# Underwater_vehicle-V3_0.net
KiCad netlist of a schematic drawn in Altium Designer
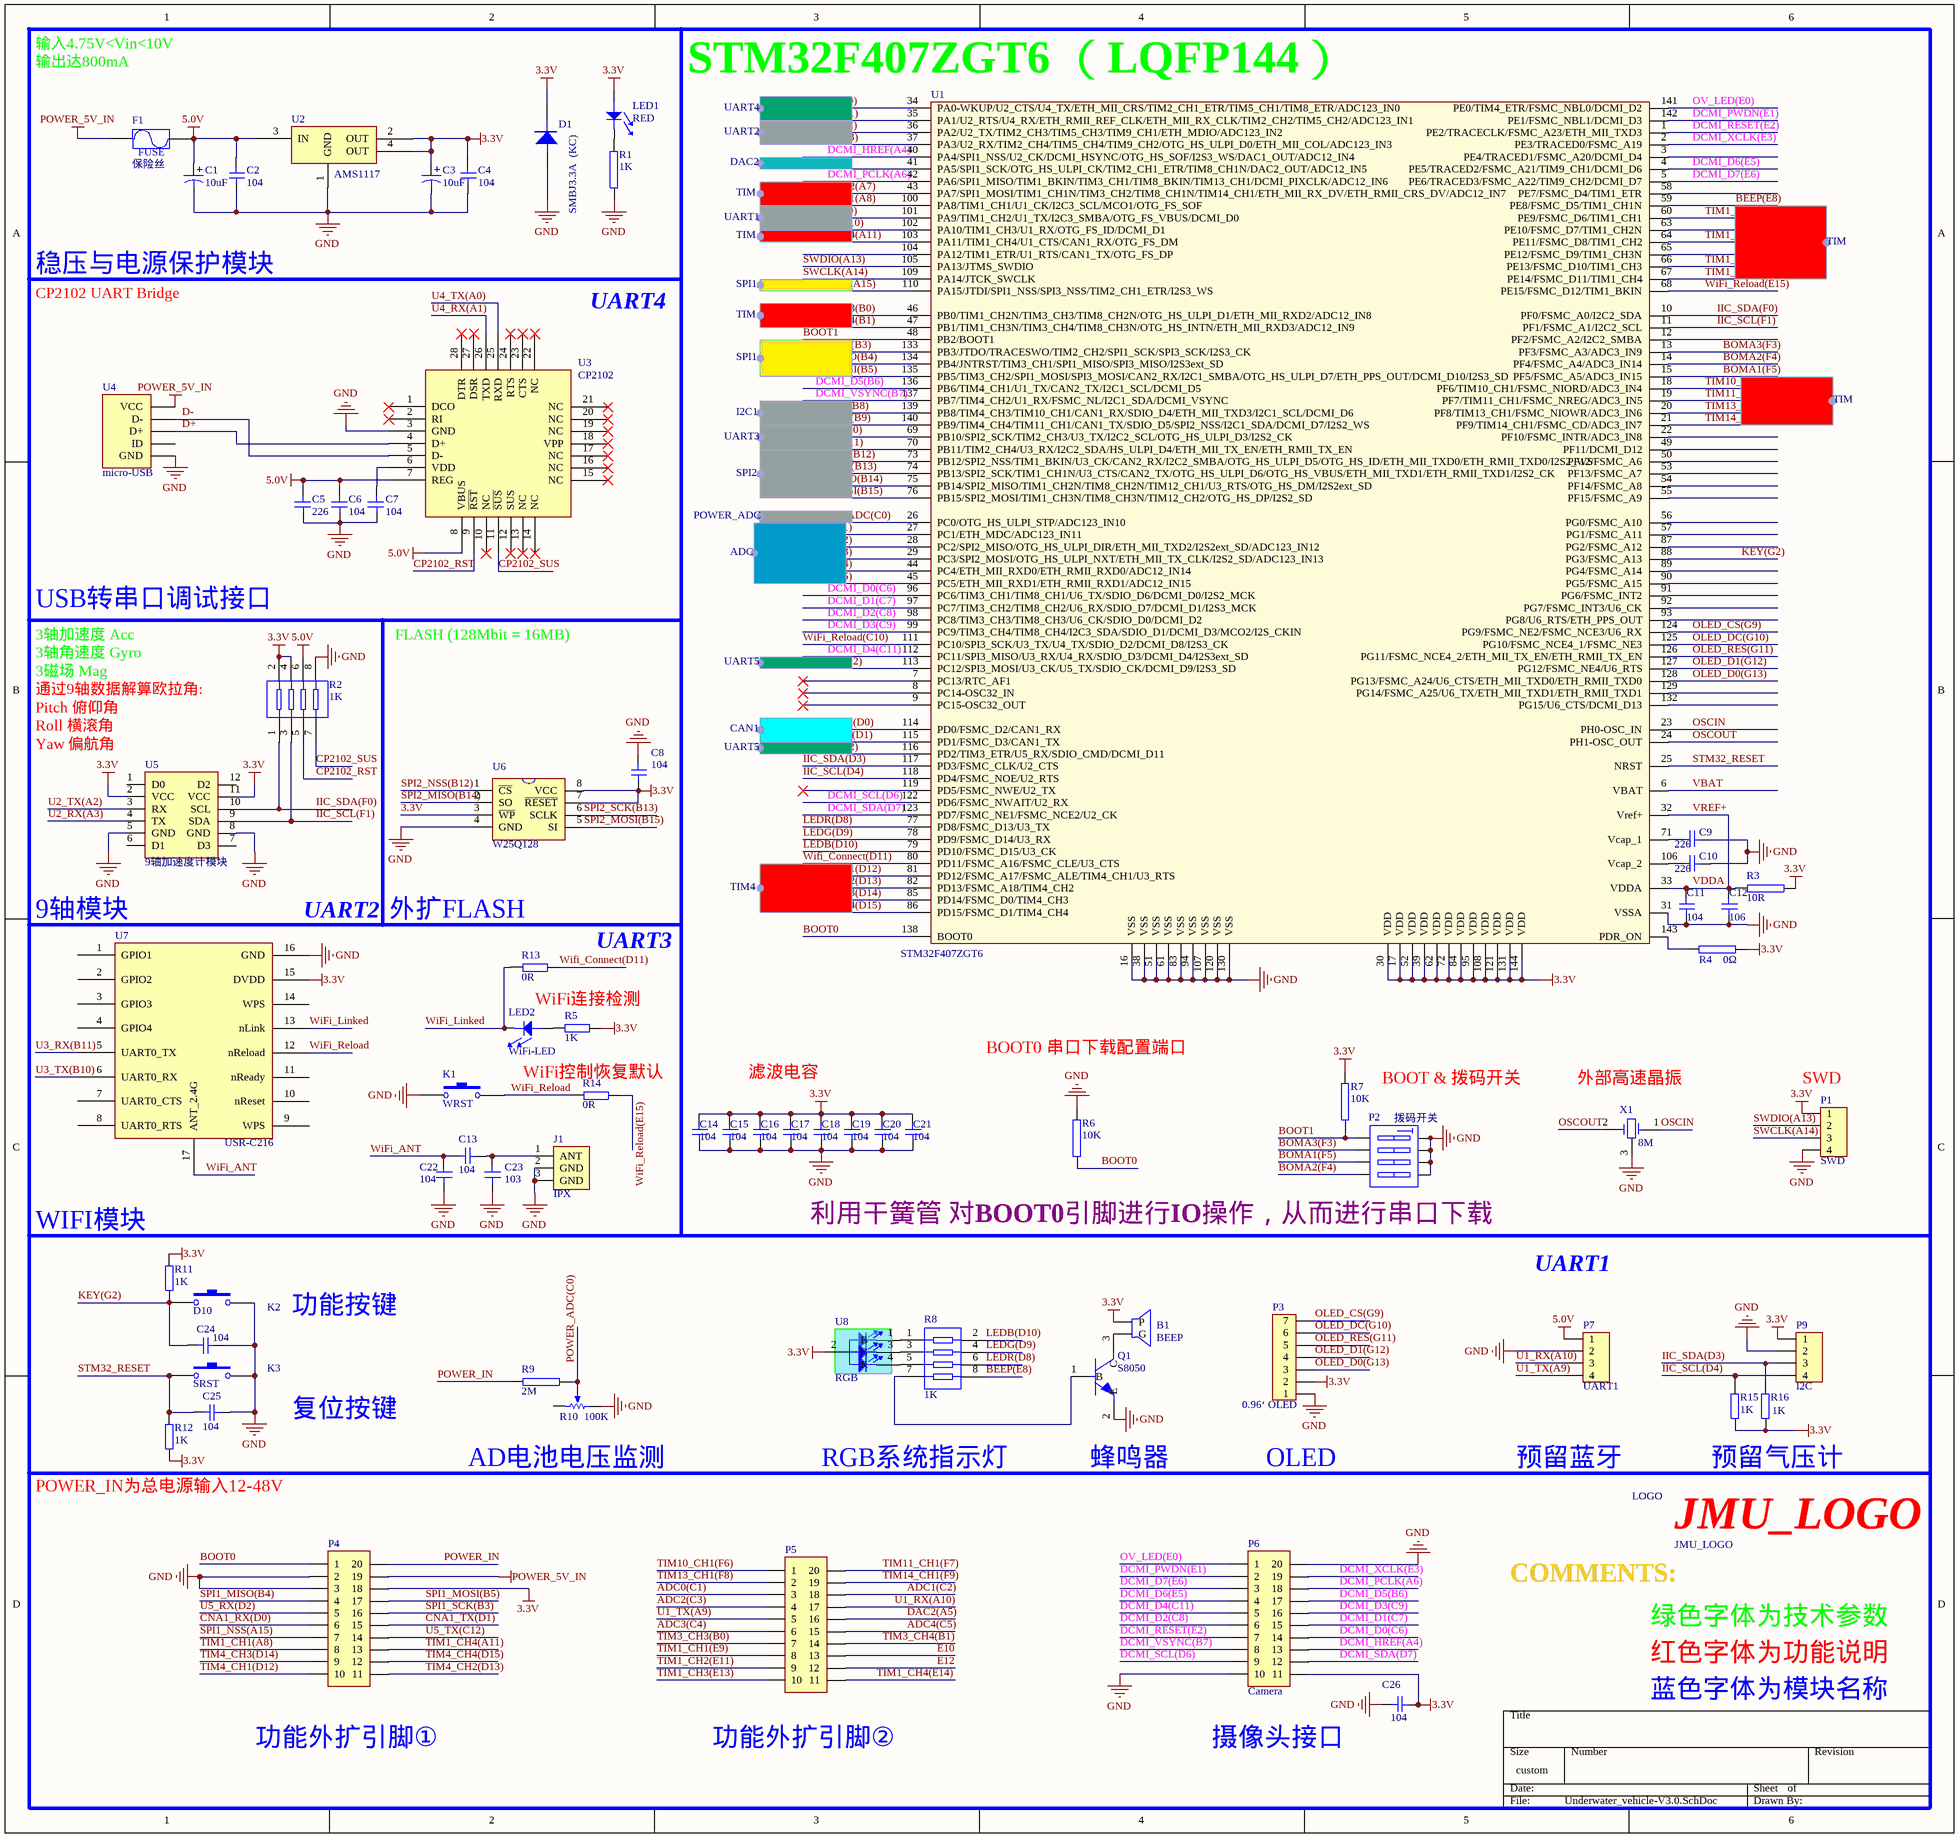
[diagram p0: Underwater_vehicle-V3.0.SchDoc]

(export (version "E")
  (design (tool "Eeschema 10.0.6"))
  (components
    (comp (ref "B1") (value "BEEP") (footprint "BUZZER") (libsource (lib "EXPLORER") (part "BEEP")))
    (comp (ref "C1")
      (value "10uF")
      (footprint "TAJ-A")
      (description "极性贴片电容")
      (libsource (lib "集大电协1.1.0") (part "Pol Cap"))
    )
    (comp (ref "C2")
      (value "104")
      (footprint "0805C")
      (description "无极贴片电容")
      (libsource (lib "集大电协1.1.0") (part "Cap1"))
    )
    (comp (ref "C3")
      (value "10uF")
      (footprint "TAJ-A")
      (description "极性贴片电容")
      (libsource (lib "集大电协1.1.0") (part "Pol Cap"))
    )
    (comp (ref "C4")
      (value "104")
      (footprint "0805C")
      (description "无极贴片电容")
      (libsource (lib "集大电协1.1.0") (part "Cap1"))
    )
    (comp (ref "C5")
      (value "226")
      (footprint "0805C")
      (description "无极贴片电容")
      (libsource (lib "集大电协1.1.0") (part "Cap1"))
    )
    (comp (ref "C6")
      (value "104")
      (footprint "0805C")
      (description "无极贴片电容")
      (libsource (lib "集大电协1.1.0") (part "Cap1"))
    )
    (comp (ref "C7")
      (value "104")
      (footprint "0805C")
      (description "无极贴片电容")
      (libsource (lib "集大电协1.1.0") (part "Cap1"))
    )
    (comp (ref "C8")
      (value "104")
      (footprint "0805C")
      (description "无极贴片电容")
      (libsource (lib "集大电协1.1.0") (part "Cap1"))
    )
    (comp (ref "C9") (value "226") (footprint "0805C") (libsource (lib "窝牛器件封装") (part "C1")))
    (comp (ref "C10") (value "226") (footprint "0805C") (libsource (lib "窝牛器件封装") (part "C1")))
    (comp (ref "C11") (value "104") (footprint "0805C") (libsource (lib "窝牛器件封装") (part "C1")))
    (comp (ref "C12") (value "106") (footprint "0805C") (libsource (lib "窝牛器件封装") (part "C1")))
    (comp (ref "C13")
      (value "104")
      (footprint "0805C")
      (description "无极贴片电容")
      (libsource (lib "集大电协1.1.2") (part "Cap1"))
    )
    (comp (ref "C14") (value "104") (footprint "0805C") (libsource (lib "窝牛器件封装") (part "C1")))
    (comp (ref "C15") (value "104") (footprint "0805C") (libsource (lib "窝牛器件封装") (part "C1")))
    (comp (ref "C16") (value "104") (footprint "0805C") (libsource (lib "窝牛器件封装") (part "C1")))
    (comp (ref "C17") (value "104") (footprint "0805C") (libsource (lib "窝牛器件封装") (part "C1")))
    (comp (ref "C18") (value "104") (footprint "0805C") (libsource (lib "窝牛器件封装") (part "C1")))
    (comp (ref "C19") (value "104") (footprint "0805C") (libsource (lib "窝牛器件封装") (part "C1")))
    (comp (ref "C20") (value "104") (footprint "0805C") (libsource (lib "窝牛器件封装") (part "C1")))
    (comp (ref "C21") (value "104") (footprint "0805C") (libsource (lib "窝牛器件封装") (part "C1")))
    (comp (ref "C22")
      (value "104")
      (footprint "0805C")
      (description "无极贴片电容")
      (libsource (lib "集大电协1.1.2") (part "Cap1"))
    )
    (comp (ref "C23")
      (value "103")
      (footprint "0805C")
      (description "无极贴片电容")
      (libsource (lib "集大电协1.1.2") (part "Cap1"))
    )
    (comp (ref "C24") (value "104") (footprint "0805C") (libsource (lib "窝牛器件封装") (part "C1")))
    (comp (ref "C25") (value "104") (footprint "0805C") (libsource (lib "窝牛器件封装") (part "C1")))
    (comp (ref "C26")
      (value "104")
      (footprint "0805C")
      (description "无极贴片电容")
      (libsource (lib "集大电协1.1.5") (part "Cap1"))
    )
    (comp (ref "D1")
      (value "SMBJ3.3A  (KC)")
      (footprint "SMBJ")
      (description "二极管")
      (libsource (lib "集大电协1.1.0") (part "Diode"))
    )
    (comp (ref "F1") (value "保险丝") (footprint "1812") (libsource (lib "集大电协1.1.2") (part "Fuse")))
    (comp (ref "J1") (value "IPX") (footprint "IPX天线底座") (libsource (lib "集大电协1.1.2") (part "IPX天线座")))
    (comp (ref "K1")
      (value "WRST")
      (footprint "贴片按键")
      (description "轻触开关")
      (libsource (lib "集大电协1.1.2") (part "轻触按键"))
    )
    (comp (ref "K2") (value "D10") (footprint "贴片按键") (libsource (lib "窝牛器件封装") (part "Key(两脚贴片)")))
    (comp (ref "K3") (value "SRST") (footprint "贴片按键") (libsource (lib "窝牛器件封装") (part "Key(两脚贴片)")))
    (comp (ref "LED1")
      (value "RED")
      (footprint "0805LED(RED)")
      (description "发光二极管")
      (libsource (lib "集大电协1.1.2") (part "LED"))
    )
    (comp (ref "LED2")
      (value "WiFi-LED")
      (footprint "0805LED(GREEN)")
      (description "发光二极管")
      (libsource (lib "集大电协1.1.2") (part "LED"))
    )
    (comp (ref "LOGO")
      (value "JMU_LOGO")
      (footprint "JMU_LOGO(1.35cm)")
      (description "LOGO")
      (libsource (lib "集大电协1.1.5") (part "JMU_LOGO"))
    )
    (comp (ref "P1")
      (value "SWD")
      (footprint "Header 4")
      (description "排针")
      (libsource (lib "集大电协1.1.0") (part "Header 4"))
    )
    (comp (ref "P2")
      (value "拨码开关")
      (footprint "拨码开关(4位贴片)")
      (description "4位拨码开关")
      (libsource (lib "集大电协1.1.2") (part "拨码开关4"))
    )
    (comp (ref "P3")
      (value "0.96‘ OLED")
      (footprint "Header 7")
      (description "排针")
      (libsource (lib "集大电协1.1.5") (part "Header 7"))
    )
    (comp (ref "P4") (value "~") (footprint "Header 10X2") (libsource (lib "集大电协1.1.2") (part "Header 10X2")))
    (comp (ref "P5") (value "~") (footprint "Header 10X2") (libsource (lib "集大电协1.1.2") (part "Header 10X2")))
    (comp (ref "P6")
      (value "Camera")
      (footprint "Header 10X2")
      (libsource (lib "集大电协1.1.2") (part "Header 10X2"))
    )
    (comp (ref "P7")
      (value "UART1")
      (footprint "Header 4(排母)")
      (description "排针")
      (libsource (lib "集大电协1.1.5") (part "Header 4"))
    )
    (comp (ref "P9")
      (value "I2C")
      (footprint "Header 4(排母)")
      (description "排针")
      (libsource (lib "集大电协1.1.5") (part "Header 4"))
    )
    (comp (ref "Q1")
      (value "S8050")
      (footprint "SOT-23")
      (description "NPN三极管")
      (libsource (lib "集大电协1.1.2") (part "NPN"))
    )
    (comp (ref "R1") (value "1K") (footprint "0805R") (libsource (lib "窝牛器件封装") (part "R1")))
    (comp (ref "R2")
      (value "1K")
      (footprint "排阻(4位贴片)")
      (description "排阻")
      (libsource (lib "集大电协1.1.2") (part "Res-4"))
    )
    (comp (ref "R3") (value "10R") (footprint "0805R") (libsource (lib "窝牛器件封装") (part "R1")))
    (comp (ref "R4") (value "0Ω") (footprint "0805R") (libsource (lib "窝牛器件封装") (part "R1")))
    (comp (ref "R5")
      (value "1K")
      (footprint "0805R")
      (description "电阻")
      (libsource (lib "集大电协1.1.2") (part "Res"))
    )
    (comp (ref "R6") (value "10K") (footprint "0805R") (libsource (lib "窝牛器件封装") (part "R1")))
    (comp (ref "R7") (value "10K") (footprint "0805R") (libsource (lib "窝牛器件封装") (part "R1")))
    (comp (ref "R8")
      (value "1K")
      (footprint "排阻(4位贴片)")
      (description "排阻")
      (libsource (lib "集大电协1.1.2") (part "Res-4"))
    )
    (comp (ref "R9") (value "2M") (footprint "0805R") (libsource (lib "窝牛器件封装") (part "R1")))
    (comp (ref "R10")
      (value "100K")
      (footprint "3296w")
      (description "电位器")
      (libsource (lib "集大电协1.1.2") (part "RPot"))
    )
    (comp (ref "R11")
      (value "1K")
      (footprint "0805R")
      (description "电阻")
      (libsource (lib "集大电协1.1.5") (part "Res"))
    )
    (comp (ref "R12")
      (value "1K")
      (footprint "0805R")
      (description "电阻")
      (libsource (lib "集大电协1.1.5") (part "Res"))
    )
    (comp (ref "R13")
      (value "0R")
      (footprint "0805R")
      (description "电阻")
      (libsource (lib "集大电协1.1.5") (part "Res"))
    )
    (comp (ref "R14")
      (value "0R")
      (footprint "0805R")
      (description "电阻")
      (libsource (lib "集大电协1.1.5") (part "Res"))
    )
    (comp (ref "R15")
      (value "1K")
      (footprint "0805R")
      (description "电阻")
      (libsource (lib "集大电协1.2") (part "Res"))
    )
    (comp (ref "R16")
      (value "1K")
      (footprint "0805R")
      (description "电阻")
      (libsource (lib "集大电协1.2") (part "Res"))
    )
    (comp (ref "U1")
      (value "STM32F407ZGT6")
      (footprint "LQFP-144")
      (libsource (lib "窝牛器件封装") (part "STM32F407ZET6"))
    )
    (comp (ref "U2")
      (value "AMS1117")
      (footprint "SOT-223")
      (description "电源芯片")
      (libsource (lib "集大电协1.1.0") (part "AMS1117-3.3V/5.0V"))
    )
    (comp (ref "U3")
      (value "CP2102")
      (footprint "QFN-28")
      (description "USB转串口芯片")
      (libsource (lib "集大电协1.1.0") (part "CP2102"))
    )
    (comp (ref "U4")
      (value "micro-USB")
      (footprint "Micro-USB (兼容牛角)")
      (description "USB接口")
      (libsource (lib "集大电协1.1.2") (part "micro-USB"))
    )
    (comp (ref "U5") (value "9轴加速度计模块") (footprint "9轴加速度计") (libsource (lib "窝牛器件封装") (part "9轴加速度计")))
    (comp (ref "U6")
      (value "W25Q128")
      (footprint "SOW-8")
      (description "FLASH芯片")
      (libsource (lib "集大电协1.1.0") (part "W25Q128"))
    )
    (comp (ref "U7")
      (value "USR-C216")
      (footprint "USR-C216")
      (libsource (lib "集大电协1.1.2") (part "USR-C216"))
    )
    (comp (ref "U8") (value "RGB") (footprint "RGB-3528") (libsource (lib "集大电协1.1.2") (part "RGB")))
    (comp (ref "X1") (value "8M") (footprint "三脚贴片8M晶振") (libsource (lib "集大电协1.1.2") (part "XTAL三脚贴片晶振")))
  )
  (nets
    (net (code "1") (name "/ADC0(C1)") (class "Default")
      (node (ref "P5") (pin "3") (pinfunction "3_3") (pintype "passive"))
      (node (ref "U1") (pin "27") (pinfunction "PC1/ETH_MDC/ADC123_IN11_27") (pintype "passive"))
    )
    (net (code "2") (name "/ADC1(C2)") (class "Default")
      (node (ref "P5") (pin "18") (pinfunction "18_18") (pintype "passive"))
      (node (ref "U1") (pin "28") (pinfunction "PC2/SPI2_MISO/OTG_HS_ULPI_DIR/ETH_MII_TXD2/I2S2ext_SD/ADC123_IN12_28") (pintype "passive"))
    )
    (net (code "3") (name "/ADC2(C3)") (class "Default")
      (node (ref "P5") (pin "4") (pinfunction "4_4") (pintype "passive"))
      (node (ref "U1") (pin "29") (pinfunction "PC3/SPI2_MOSI/OTG_HS_ULPI_NXT/ETH_MII_TX_CLK/I2S2_SD/ADC123_IN13_29") (pintype "passive"))
    )
    (net (code "4") (name "/ADC3(C4)") (class "Default")
      (node (ref "P5") (pin "6") (pinfunction "6_6") (pintype "passive"))
      (node (ref "U1") (pin "44") (pinfunction "PC4/ETH_MII_RXD0/ETH_RMII_RXD0/ADC12_IN14_44") (pintype "passive"))
    )
    (net (code "5") (name "/ADC4(C5)") (class "Default")
      (node (ref "P5") (pin "15") (pinfunction "15_15") (pintype "passive"))
      (node (ref "U1") (pin "45") (pinfunction "PC5/ETH_MII_RXD1/ETH_RMII_RXD1/ADC12_IN15_45") (pintype "passive"))
    )
    (net (code "6") (name "/BEEP(E8)") (class "Default")
      (node (ref "R8") (pin "8") (pinfunction "8_8") (pintype "passive"))
      (node (ref "U1") (pin "59") (pinfunction "PE8/FSMC_D5/TIM1_CH1N_59") (pintype "passive"))
    )
    (net (code "7") (name "/BOMA1(F5)") (class "Default")
      (node (ref "P2") (pin "3") (pinfunction "A3_3") (pintype "passive"))
      (node (ref "U1") (pin "15") (pinfunction "PF5/FSMC_A5/ADC3_IN15_15") (pintype "passive"))
    )
    (net (code "8") (name "/BOMA2(F4)") (class "Default")
      (node (ref "P2") (pin "4") (pinfunction "A4_4") (pintype "passive"))
      (node (ref "U1") (pin "14") (pinfunction "PF4/FSMC_A4/ADC3_IN14_14") (pintype "passive"))
    )
    (net (code "9") (name "/BOMA3(F3)") (class "Default")
      (node (ref "P2") (pin "2") (pinfunction "A2_2") (pintype "passive"))
      (node (ref "U1") (pin "13") (pinfunction "PF3/FSMC_A3/ADC3_IN9_13") (pintype "passive"))
    )
    (net (code "10") (name "/BOOT0") (class "Default")
      (node (ref "P4") (pin "1") (pinfunction "1_1") (pintype "passive"))
      (node (ref "R6") (pin "1") (pinfunction "1_1") (pintype "passive"))
      (node (ref "U1") (pin "138") (pinfunction "BOOT0_138") (pintype "passive"))
    )
    (net (code "11") (name "/BOOT1") (class "Default")
      (node (ref "P2") (pin "1") (pinfunction "A1_1") (pintype "passive"))
      (node (ref "R7") (pin "1") (pinfunction "1_1") (pintype "passive"))
      (node (ref "U1") (pin "48") (pinfunction "PB2/BOOT1_48") (pintype "passive"))
    )
    (net (code "12") (name "/CNA1_RX(D0)") (class "Default")
      (node (ref "P4") (pin "6") (pinfunction "6_6") (pintype "passive"))
      (node (ref "U1") (pin "114") (pinfunction "PD0/FSMC_D2/CAN1_RX_114") (pintype "passive"))
    )
    (net (code "13") (name "/CNA1_TX(D1)") (class "Default")
      (node (ref "P4") (pin "15") (pinfunction "15_15") (pintype "passive"))
      (node (ref "U1") (pin "115") (pinfunction "PD1/FSMC_D3/CAN1_TX_115") (pintype "passive"))
    )
    (net (code "14") (name "/CP2102_RST") (class "Default")
      (node (ref "R2") (pin "5") (pinfunction "5_5") (pintype "passive"))
      (node (ref "U3") (pin "9") (pinfunction "~{RST}_9") (pintype "passive"))
    )
    (net (code "15") (name "/CP2102_SUS") (class "Default")
      (node (ref "R2") (pin "7") (pinfunction "7_7") (pintype "passive"))
      (node (ref "U3") (pin "11") (pinfunction "~{SUS}_11") (pintype "passive"))
    )
    (net (code "16") (name "/D+") (class "Default")
      (node (ref "U3") (pin "4") (pinfunction "D+_4") (pintype "passive"))
      (node (ref "U4") (pin "3") (pinfunction "D+_3") (pintype "power_in"))
    )
    (net (code "17") (name "/D-") (class "Default")
      (node (ref "U3") (pin "5") (pinfunction "D-_5") (pintype "passive"))
      (node (ref "U4") (pin "2") (pinfunction "D-_2") (pintype "power_in"))
    )
    (net (code "18") (name "/DAC2(A5)") (class "Default")
      (node (ref "P5") (pin "16") (pinfunction "16_16") (pintype "passive"))
      (node (ref "U1") (pin "41") (pinfunction "PA5/SPI1_SCK/OTG_HS_ULPI_CK/TIM2_CH1_ETR/TIM8_CH1N/DAC2_OUT/ADC12_IN5_41") (pintype "passive"))
    )
    (net (code "19") (name "/DCMI_D0(C6)") (class "Default")
      (node (ref "P6") (pin "14") (pinfunction "14_14") (pintype "passive"))
      (node (ref "U1") (pin "96") (pinfunction "PC6/TIM3_CH1/TIM8_CH1/U6_TX/SDIO_D6/DCMI_D0/I2S2_MCK_96") (pintype "passive"))
    )
    (net (code "20") (name "/DCMI_D1(C7)") (class "Default")
      (node (ref "P6") (pin "15") (pinfunction "15_15") (pintype "passive"))
      (node (ref "U1") (pin "97") (pinfunction "PC7/TIM3_CH2/TIM8_CH2/U6_RX/SDIO_D7/DCMI_D1/I2S3_MCK_97") (pintype "passive"))
    )
    (net (code "21") (name "/DCMI_D2(C8)") (class "Default")
      (node (ref "P6") (pin "6") (pinfunction "6_6") (pintype "passive"))
      (node (ref "U1") (pin "98") (pinfunction "PC8/TIM3_CH3/TIM8_CH3/U6_CK/SDIO_D0/DCMI_D2_98") (pintype "passive"))
    )
    (net (code "22") (name "/DCMI_D3(C9)") (class "Default")
      (node (ref "P6") (pin "16") (pinfunction "16_16") (pintype "passive"))
      (node (ref "U1") (pin "99") (pinfunction "PC9/TIM3_CH4/TIM8_CH4/I2C3_SDA/SDIO_D1/DCMI_D3/MCO2/I2S_CKIN_99") (pintype "passive"))
    )
    (net (code "23") (name "/DCMI_D4(C11)") (class "Default")
      (node (ref "P6") (pin "5") (pinfunction "5_5") (pintype "passive"))
      (node (ref "U1") (pin "112") (pinfunction "PC11/SPI3_MISO/U3_RX/U4_RX/SDIO_D3/DCMI_D4/I2S3ext_SD_112") (pintype "passive"))
    )
    (net (code "24") (name "/DCMI_D5(B6)") (class "Default")
      (node (ref "P6") (pin "17") (pinfunction "17_17") (pintype "passive"))
      (node (ref "U1") (pin "136") (pinfunction "PB6/TIM4_CH1/U1_TX/CAN2_TX/I2C1_SCL/DCMI_D5_136") (pintype "passive"))
    )
    (net (code "25") (name "/DCMI_D6(E5)") (class "Default")
      (node (ref "P6") (pin "4") (pinfunction "4_4") (pintype "passive"))
      (node (ref "U1") (pin "4") (pinfunction "PE5/TRACED2/FSMC_A21/TIM9_CH1/DCMI_D6_4") (pintype "passive"))
    )
    (net (code "26") (name "/DCMI_D7(E6)") (class "Default")
      (node (ref "P6") (pin "3") (pinfunction "3_3") (pintype "passive"))
      (node (ref "U1") (pin "5") (pinfunction "PE6/TRACED3/FSMC_A22/TIM9_CH2/DCMI_D7_5") (pintype "passive"))
    )
    (net (code "27") (name "/DCMI_HREF(A4)") (class "Default")
      (node (ref "P6") (pin "13") (pinfunction "13_13") (pintype "passive"))
      (node (ref "U1") (pin "40") (pinfunction "PA4/SPI1_NSS/U2_CK/DCMI_HSYNC/OTG_HS_SOF/I2S3_WS/DAC1_OUT/ADC12_IN4_40") (pintype "passive"))
    )
    (net (code "28") (name "/DCMI_PCLK(A6)") (class "Default")
      (node (ref "P6") (pin "18") (pinfunction "18_18") (pintype "passive"))
      (node (ref "U1") (pin "42") (pinfunction "PA6/SPI1_MISO/TIM1_BKIN/TIM3_CH1/TIM8_BKIN/TIM13_CH1/DCMI_PIXCLK/ADC12_IN6_42") (pintype "passive"))
    )
    (net (code "29") (name "/DCMI_PWDN(E1)") (class "Default")
      (node (ref "P6") (pin "2") (pinfunction "2_2") (pintype "passive"))
      (node (ref "U1") (pin "142") (pinfunction "PE1/FSMC_NBL1/DCMI_D3_142") (pintype "passive"))
    )
    (net (code "30") (name "/DCMI_RESET(E2)") (class "Default")
      (node (ref "P6") (pin "7") (pinfunction "7_7") (pintype "passive"))
      (node (ref "U1") (pin "1") (pinfunction "PE2/TRACECLK/FSMC_A23/ETH_MII_TXD3_1") (pintype "passive"))
    )
    (net (code "31") (name "/DCMI_SCL(D6)") (class "Default")
      (node (ref "P6") (pin "9") (pinfunction "9_9") (pintype "passive"))
      (node (ref "U1") (pin "122") (pinfunction "PD6/FSMC_NWAIT/U2_RX_122") (pintype "passive"))
    )
    (net (code "32") (name "/DCMI_SDA(D7)") (class "Default")
      (node (ref "P6") (pin "12") (pinfunction "12_12") (pintype "passive"))
      (node (ref "U1") (pin "123") (pinfunction "PD7/FSMC_NE1/FSMC_NCE2/U2_CK_123") (pintype "passive"))
    )
    (net (code "33") (name "/DCMI_VSYNC(B7)") (class "Default")
      (node (ref "P6") (pin "8") (pinfunction "8_8") (pintype "passive"))
      (node (ref "U1") (pin "137") (pinfunction "PB7/TIM4_CH2/U1_RX/FSMC_NL/I2C1_SDA/DCMI_VSYNC_137") (pintype "passive"))
    )
    (net (code "34") (name "/DCMI_XCLK(E3)") (class "Default")
      (node (ref "P6") (pin "19") (pinfunction "19_19") (pintype "passive"))
      (node (ref "U1") (pin "2") (pinfunction "PE3/TRACED0/FSMC_A19_2") (pintype "passive"))
    )
    (net (code "35") (name "/E10") (class "Default")
      (node (ref "P5") (pin "13") (pinfunction "13_13") (pintype "passive"))
      (node (ref "U1") (pin "63") (pinfunction "PE10/FSMC_D7/TIM1_CH2N_63") (pintype "passive"))
    )
    (net (code "36") (name "/E12") (class "Default")
      (node (ref "P5") (pin "12") (pinfunction "12_12") (pintype "passive"))
      (node (ref "U1") (pin "65") (pinfunction "PE12/FSMC_D9/TIM1_CH3N_65") (pintype "passive"))
    )
    (net (code "37") (name "/IIC1_SCL(B8)") (class "Default")
      (node (ref "U1") (pin "139") (pinfunction "PB8/TIM4_CH3/TIM10_CH1/CAN1_RX/SDIO_D4/ETH_MII_TXD3/I2C1_SCL/DCMI_D6_139") (pintype "passive"))
    )
    (net (code "38") (name "/IIC1_SDA(B9)") (class "Default")
      (node (ref "U1") (pin "140") (pinfunction "PB9/TIM4_CH4/TIM11_CH1/CAN1_TX/SDIO_D5/SPI2_NSS/I2C1_SDA/DCMI_D7/I2S2_WS_140") (pintype "passive"))
    )
    (net (code "39") (name "/IIC_SCL(D4)") (class "Default")
      (node (ref "P9") (pin "4") (pinfunction "4_4") (pintype "passive"))
      (node (ref "R15") (pin "2") (pinfunction "2_2") (pintype "passive"))
      (node (ref "U1") (pin "118") (pinfunction "PD4/FSMC_NOE/U2_RTS_118") (pintype "passive"))
    )
    (net (code "40") (name "/IIC_SCL(F1)") (class "Default")
      (node (ref "R2") (pin "3") (pinfunction "3_3") (pintype "passive"))
      (node (ref "U1") (pin "11") (pinfunction "PF1/FSMC_A1/I2C2_SCL_11") (pintype "passive"))
      (node (ref "U5") (pin "9") (pinfunction "SDA_9") (pintype "passive"))
    )
    (net (code "41") (name "/IIC_SDA(D3)") (class "Default")
      (node (ref "P9") (pin "3") (pinfunction "3_3") (pintype "passive"))
      (node (ref "R16") (pin "2") (pinfunction "2_2") (pintype "passive"))
      (node (ref "U1") (pin "117") (pinfunction "PD3/FSMC_CLK/U2_CTS_117") (pintype "passive"))
    )
    (net (code "42") (name "/IIC_SDA(F0)") (class "Default")
      (node (ref "R2") (pin "1") (pinfunction "1_1") (pintype "passive"))
      (node (ref "U1") (pin "10") (pinfunction "PF0/FSMC_A0/I2C2_SDA_10") (pintype "passive"))
      (node (ref "U5") (pin "10") (pinfunction "SCL_10") (pintype "passive"))
    )
    (net (code "43") (name "/KEY(G2)") (class "Default")
      (node (ref "C24") (pin "1") (pinfunction "1_1") (pintype "passive"))
      (node (ref "K2") (pin "1") (pinfunction "1_1") (pintype "passive"))
      (node (ref "R11") (pin "1") (pinfunction "1_1") (pintype "passive"))
      (node (ref "U1") (pin "88") (pinfunction "PG3/FSMC_A13_88") (pintype "passive"))
    )
    (net (code "44") (name "/LEDB(D10)") (class "Default")
      (node (ref "R8") (pin "2") (pinfunction "2_2") (pintype "passive"))
      (node (ref "U1") (pin "79") (pinfunction "PD10/FSMC_D15/U3_CK_79") (pintype "passive"))
    )
    (net (code "45") (name "/LEDG(D9)") (class "Default")
      (node (ref "R8") (pin "4") (pinfunction "4_4") (pintype "passive"))
      (node (ref "U1") (pin "78") (pinfunction "PD9/FSMC_D14/U3_RX_78") (pintype "passive"))
    )
    (net (code "46") (name "/LEDR(D8)") (class "Default")
      (node (ref "R8") (pin "6") (pinfunction "6_6") (pintype "passive"))
      (node (ref "U1") (pin "77") (pinfunction "PD8/FSMC_D13/U3_TX_77") (pintype "passive"))
    )
    (net (code "47") (name "/OLED_CS(G9)") (class "Default")
      (node (ref "P3") (pin "7") (pinfunction "7_7") (pintype "passive"))
      (node (ref "U1") (pin "124") (pinfunction "PG9/FSMC_NE2/FSMC_NCE3/U6_RX_124") (pintype "passive"))
    )
    (net (code "48") (name "/OLED_D0(G13)") (class "Default")
      (node (ref "P3") (pin "3") (pinfunction "3_3") (pintype "passive"))
      (node (ref "U1") (pin "128") (pinfunction "PG13/FSMC_A24/U6_CTS/ETH_MII_TXD0/ETH_RMII_TXD0_128") (pintype "passive"))
    )
    (net (code "49") (name "/OLED_D1(G12)") (class "Default")
      (node (ref "P3") (pin "4") (pinfunction "4_4") (pintype "passive"))
      (node (ref "U1") (pin "127") (pinfunction "PG12/FSMC_NE4/U6_RTS_127") (pintype "passive"))
    )
    (net (code "50") (name "/OLED_DC(G10)") (class "Default")
      (node (ref "P3") (pin "6") (pinfunction "6_6") (pintype "passive"))
      (node (ref "U1") (pin "125") (pinfunction "PG10/FSMC_NCE4_1/FSMC_NE3_125") (pintype "passive"))
    )
    (net (code "51") (name "/OLED_RES(G11)") (class "Default")
      (node (ref "P3") (pin "5") (pinfunction "5_5") (pintype "passive"))
      (node (ref "U1") (pin "126") (pinfunction "PG11/FSMC_NCE4_2/ETH_MII_TX_EN/ETH_RMII_TX_EN_126") (pintype "passive"))
    )
    (net (code "52") (name "/OSCIN") (class "Default")
      (node (ref "U1") (pin "23") (pinfunction "PH0-OSC_IN_23") (pintype "passive"))
      (node (ref "X1") (pin "1") (pinfunction "1_1") (pintype "passive"))
    )
    (net (code "53") (name "/OSCOUT") (class "Default")
      (node (ref "U1") (pin "24") (pinfunction "PH1-OSC_OUT_24") (pintype "passive"))
      (node (ref "X1") (pin "2") (pinfunction "2_2") (pintype "passive"))
    )
    (net (code "54") (name "/OV_LED(E0)") (class "Default")
      (node (ref "P6") (pin "1") (pinfunction "1_1") (pintype "passive"))
      (node (ref "U1") (pin "141") (pinfunction "PE0/TIM4_ETR/FSMC_NBL0/DCMI_D2_141") (pintype "passive"))
    )
    (net (code "55") (name "/POWER_ADC(C0)") (class "Default")
      (node (ref "R10") (pin "2") (pinfunction "TAP_2") (pintype "passive"))
      (node (ref "R9") (pin "2") (pinfunction "2_2") (pintype "passive"))
      (node (ref "U1") (pin "26") (pinfunction "PC0/OTG_HS_ULPI_STP/ADC123_IN10_26") (pintype "passive"))
    )
    (net (code "56") (name "/POWER_IN") (class "Default")
      (node (ref "P4") (pin "20") (pinfunction "20_20") (pintype "passive"))
      (node (ref "R9") (pin "1") (pinfunction "1_1") (pintype "passive"))
    )
    (net (code "57") (name "/SPI1_MISO(B4)") (class "Default")
      (node (ref "P4") (pin "4") (pinfunction "4_4") (pintype "passive"))
      (node (ref "U1") (pin "134") (pinfunction "PB4/JNTRST/TIM3_CH1/SPI1_MISO/SPI3_MISO/I2S3ext_SD_134") (pintype "passive"))
    )
    (net (code "58") (name "/SPI1_MOSI(B5)") (class "Default")
      (node (ref "P4") (pin "17") (pinfunction "17_17") (pintype "passive"))
      (node (ref "U1") (pin "135") (pinfunction "PB5/TIM3_CH2/SPI1_MOSI/SPI3_MOSI/CAN2_RX/I2C1_SMBA/OTG_HS_ULPI_D7/ETH_PPS_OUT/DCMI_D10/I2S3_SD_135") (pintype "passive"))
    )
    (net (code "59") (name "/SPI1_NSS(A15)") (class "Default")
      (node (ref "P4") (pin "7") (pinfunction "7_7") (pintype "passive"))
      (node (ref "U1") (pin "110") (pinfunction "PA15/JTDI/SPI1_NSS/SPI3_NSS/TIM2_CH1_ETR/I2S3_WS_110") (pintype "passive"))
    )
    (net (code "60") (name "/SPI1_SCK(B3)") (class "Default")
      (node (ref "P4") (pin "16") (pinfunction "16_16") (pintype "passive"))
      (node (ref "U1") (pin "133") (pinfunction "PB3/JTDO/TRACESWO/TIM2_CH2/SPI1_SCK/SPI3_SCK/I2S3_CK_133") (pintype "passive"))
    )
    (net (code "61") (name "/SPI2_MISO(B14)") (class "Default")
      (node (ref "U1") (pin "75") (pinfunction "PB14/SPI2_MISO/TIM1_CH2N/TIM8_CH2N/TIM12_CH1/U3_RTS/OTG_HS_DM/I2S2ext_SD_75") (pintype "passive"))
      (node (ref "U6") (pin "2") (pinfunction "SO_2") (pintype "passive"))
    )
    (net (code "62") (name "/SPI2_MOSI(B15)") (class "Default")
      (node (ref "U1") (pin "76") (pinfunction "PB15/SPI2_MOSI/TIM1_CH3N/TIM8_CH3N/TIM12_CH2/OTG_HS_DP/I2S2_SD_76") (pintype "passive"))
      (node (ref "U6") (pin "5") (pinfunction "SI_5") (pintype "passive"))
    )
    (net (code "63") (name "/SPI2_NSS(B12)") (class "Default")
      (node (ref "U1") (pin "73") (pinfunction "PB12/SPI2_NSS/TIM1_BKIN/U3_CK/CAN2_RX/I2C2_SMBA/OTG_HS_ULPI_D5/OTG_HS_ID/ETH_MII_TXD0/ETH_RMII_TXD0/I2S2_WS_73") (pintype "passive"))
      (node (ref "U6") (pin "1") (pinfunction "~{CS}_1") (pintype "passive"))
    )
    (net (code "64") (name "/SPI2_SCK(B13)") (class "Default")
      (node (ref "U1") (pin "74") (pinfunction "PB13/SPI2_SCK/TIM1_CH1N/U3_CTS/CAN2_TX/OTG_HS_ULPI_D6/OTG_HS_VBUS/ETH_MII_TXD1/ETH_RMII_TXD1/I2S2_CK_74") (pintype "passive"))
      (node (ref "U6") (pin "6") (pinfunction "SCLK_6") (pintype "passive"))
    )
    (net (code "65") (name "/STM32_RESET") (class "Default")
      (node (ref "C25") (pin "1") (pinfunction "1_1") (pintype "passive"))
      (node (ref "K3") (pin "1") (pinfunction "1_1") (pintype "passive"))
      (node (ref "R12") (pin "2") (pinfunction "2_2") (pintype "passive"))
      (node (ref "U1") (pin "25") (pinfunction "NRST_25") (pintype "passive"))
    )
    (net (code "66") (name "/SWCLK(A14)") (class "Default")
      (node (ref "P1") (pin "3") (pinfunction "3_3") (pintype "passive"))
      (node (ref "U1") (pin "109") (pinfunction "PA14/JTCK_SWCLK_109") (pintype "passive"))
    )
    (net (code "67") (name "/SWDIO(A13)") (class "Default")
      (node (ref "P1") (pin "2") (pinfunction "2_2") (pintype "passive"))
      (node (ref "U1") (pin "105") (pinfunction "PA13/JTMS_SWDIO_105") (pintype "passive"))
    )
    (net (code "68") (name "/TIM1_CH1(A8)") (class "Default")
      (node (ref "P4") (pin "8") (pinfunction "8_8") (pintype "passive"))
      (node (ref "U1") (pin "100") (pinfunction "PA8/TIM1_CH1/U1_CK/I2C3_SCL/MCO1/OTG_FS_SOF_100") (pintype "passive"))
    )
    (net (code "69") (name "/TIM1_CH1(E9)") (class "Default")
      (node (ref "P5") (pin "8") (pinfunction "8_8") (pintype "passive"))
      (node (ref "U1") (pin "60") (pinfunction "PE9/FSMC_D6/TIM1_CH1_60") (pintype "passive"))
    )
    (net (code "70") (name "/TIM1_CH2(E11)") (class "Default")
      (node (ref "P5") (pin "9") (pinfunction "9_9") (pintype "passive"))
      (node (ref "U1") (pin "64") (pinfunction "PE11/FSMC_D8/TIM1_CH2_64") (pintype "passive"))
    )
    (net (code "71") (name "/TIM1_CH3(E13)") (class "Default")
      (node (ref "P5") (pin "10") (pinfunction "10_10") (pintype "passive"))
      (node (ref "U1") (pin "66") (pinfunction "PE13/FSMC_D10/TIM1_CH3_66") (pintype "passive"))
    )
    (net (code "72") (name "/TIM1_CH4(A11)") (class "Default")
      (node (ref "P4") (pin "13") (pinfunction "13_13") (pintype "passive"))
      (node (ref "U1") (pin "103") (pinfunction "PA11/TIM1_CH4/U1_CTS/CAN1_RX/OTG_FS_DM_103") (pintype "passive"))
    )
    (net (code "73") (name "/TIM1_CH4(E14)") (class "Default")
      (node (ref "P5") (pin "11") (pinfunction "11_11") (pintype "passive"))
      (node (ref "U1") (pin "67") (pinfunction "PE14/FSMC_D11/TIM1_CH4_67") (pintype "passive"))
    )
    (net (code "74") (name "/TIM3_CH2(A7)") (class "Default")
      (node (ref "U1") (pin "43") (pinfunction "PA7/SPI1_MOSI/TIM1_CH1N/TIM3_CH2/TIM8_CH1N/TIM14_CH1/ETH_MII_RX_DV/ETH_RMII_CRS_DV/ADC12_IN7_43") (pintype "passive"))
    )
    (net (code "75") (name "/TIM3_CH3(B0)") (class "Default")
      (node (ref "P5") (pin "7") (pinfunction "7_7") (pintype "passive"))
      (node (ref "U1") (pin "46") (pinfunction "PB0/TIM1_CH2N/TIM3_CH3/TIM8_CH2N/OTG_HS_ULPI_D1/ETH_MII_RXD2/ADC12_IN8_46") (pintype "passive"))
    )
    (net (code "76") (name "/TIM3_CH4(B1)") (class "Default")
      (node (ref "P5") (pin "14") (pinfunction "14_14") (pintype "passive"))
      (node (ref "U1") (pin "47") (pinfunction "PB1/TIM1_CH3N/TIM3_CH4/TIM8_CH3N/OTG_HS_INTN/ETH_MII_RXD3/ADC12_IN9_47") (pintype "passive"))
    )
    (net (code "77") (name "/TIM4_CH1(D12)") (class "Default")
      (node (ref "P4") (pin "10") (pinfunction "10_10") (pintype "passive"))
      (node (ref "U1") (pin "81") (pinfunction "PD12/FSMC_A17/FSMC_ALE/TIM4_CH1/U3_RTS_81") (pintype "passive"))
    )
    (net (code "78") (name "/TIM4_CH2(D13)") (class "Default")
      (node (ref "P4") (pin "11") (pinfunction "11_11") (pintype "passive"))
      (node (ref "U1") (pin "82") (pinfunction "PD13/FSMC_A18/TIM4_CH2_82") (pintype "passive"))
    )
    (net (code "79") (name "/TIM4_CH3(D14)") (class "Default")
      (node (ref "P4") (pin "9") (pinfunction "9_9") (pintype "passive"))
      (node (ref "U1") (pin "85") (pinfunction "PD14/FSMC_D0/TIM4_CH3_85") (pintype "passive"))
    )
    (net (code "80") (name "/TIM4_CH4(D15)") (class "Default")
      (node (ref "P4") (pin "12") (pinfunction "12_12") (pintype "passive"))
      (node (ref "U1") (pin "86") (pinfunction "PD15/FSMC_D1/TIM4_CH4_86") (pintype "passive"))
    )
    (net (code "81") (name "/TIM10_CH1(F6)") (class "Default")
      (node (ref "P5") (pin "1") (pinfunction "1_1") (pintype "passive"))
      (node (ref "U1") (pin "18") (pinfunction "PF6/TIM10_CH1/FSMC_NIORD/ADC3_IN4_18") (pintype "passive"))
    )
    (net (code "82") (name "/TIM11_CH1(F7)") (class "Default")
      (node (ref "P5") (pin "20") (pinfunction "20_20") (pintype "passive"))
      (node (ref "U1") (pin "19") (pinfunction "PF7/TIM11_CH1/FSMC_NREG/ADC3_IN5_19") (pintype "passive"))
    )
    (net (code "83") (name "/TIM13_CH1(F8)") (class "Default")
      (node (ref "P5") (pin "2") (pinfunction "2_2") (pintype "passive"))
      (node (ref "U1") (pin "20") (pinfunction "PF8/TIM13_CH1/FSMC_NIOWR/ADC3_IN6_20") (pintype "passive"))
    )
    (net (code "84") (name "/TIM14_CH1(F9)") (class "Default")
      (node (ref "P5") (pin "19") (pinfunction "19_19") (pintype "passive"))
      (node (ref "U1") (pin "21") (pinfunction "PF9/TIM14_CH1/FSMC_CD/ADC3_IN7_21") (pintype "passive"))
    )
    (net (code "85") (name "/U1_RX(A10)") (class "Default")
      (node (ref "P5") (pin "17") (pinfunction "17_17") (pintype "passive"))
      (node (ref "P7") (pin "3") (pinfunction "3_3") (pintype "passive"))
      (node (ref "U1") (pin "102") (pinfunction "PA10/TIM1_CH3/U1_RX/OTG_FS_ID/DCMI_D1_102") (pintype "passive"))
    )
    (net (code "86") (name "/U1_TX(A9)") (class "Default")
      (node (ref "P5") (pin "5") (pinfunction "5_5") (pintype "passive"))
      (node (ref "P7") (pin "4") (pinfunction "4_4") (pintype "passive"))
      (node (ref "U1") (pin "101") (pinfunction "PA9/TIM1_CH2/U1_TX/I2C3_SMBA/OTG_FS_VBUS/DCMI_D0_101") (pintype "passive"))
    )
    (net (code "87") (name "/U2_RX(A3)") (class "Default")
      (node (ref "U1") (pin "37") (pinfunction "PA3/U2_RX/TIM2_CH4/TIM5_CH4/TIM9_CH2/OTG_HS_ULPI_D0/ETH_MII_COL/ADC123_IN3_37") (pintype "passive"))
      (node (ref "U5") (pin "4") (pinfunction "TX_4") (pintype "passive"))
    )
    (net (code "88") (name "/U2_TX(A2)") (class "Default")
      (node (ref "U1") (pin "36") (pinfunction "PA2/U2_TX/TIM2_CH3/TIM5_CH3/TIM9_CH1/ETH_MDIO/ADC123_IN2_36") (pintype "passive"))
      (node (ref "U5") (pin "3") (pinfunction "RX_3") (pintype "passive"))
    )
    (net (code "89") (name "/U3_RX(B11)") (class "Default")
      (node (ref "U1") (pin "70") (pinfunction "PB11/TIM2_CH4/U3_RX/I2C2_SDA/HS_ULPI_D4/ETH_MII_TX_EN/ETH_RMII_TX_EN_70") (pintype "passive"))
      (node (ref "U7") (pin "5") (pinfunction "UART0_TX_5") (pintype "passive"))
    )
    (net (code "90") (name "/U3_TX(B10)") (class "Default")
      (node (ref "U1") (pin "69") (pinfunction "PB10/SPI2_SCK/TIM2_CH3/U3_TX/I2C2_SCL/OTG_HS_ULPI_D3/I2S2_CK_69") (pintype "passive"))
      (node (ref "U7") (pin "6") (pinfunction "UART0_RX_6") (pintype "passive"))
    )
    (net (code "91") (name "/U4_RX(A1)") (class "Default")
      (node (ref "U1") (pin "35") (pinfunction "PA1/U2_RTS/U4_RX/ETH_RMII_REF_CLK/ETH_MII_RX_CLK/TIM2_CH2/TIM5_CH2/ADC123_IN1_35") (pintype "passive"))
      (node (ref "U3") (pin "26") (pinfunction "TXD_26") (pintype "passive"))
    )
    (net (code "92") (name "/U4_TX(A0)") (class "Default")
      (node (ref "U1") (pin "34") (pinfunction "PA0-WKUP/U2_CTS/U4_TX/ETH_MII_CRS/TIM2_CH1_ETR/TIM5_CH1/TIM8_ETR/ADC123_IN0_34") (pintype "passive"))
      (node (ref "U3") (pin "25") (pinfunction "RXD_25") (pintype "passive"))
    )
    (net (code "93") (name "/U5_RX(D2)") (class "Default")
      (node (ref "P4") (pin "5") (pinfunction "5_5") (pintype "passive"))
      (node (ref "U1") (pin "116") (pinfunction "PD2/TIM3_ETR/U5_RX/SDIO_CMD/DCMI_D11_116") (pintype "passive"))
    )
    (net (code "94") (name "/U5_TX(C12)") (class "Default")
      (node (ref "P4") (pin "14") (pinfunction "14_14") (pintype "passive"))
      (node (ref "U1") (pin "113") (pinfunction "PC12/SPI3_MOSI/U3_CK/U5_TX/SDIO_CK/DCMI_D9/I2S3_SD_113") (pintype "passive"))
    )
    (net (code "95") (name "/VBAT") (class "Default")
      (node (ref "U1") (pin "6") (pinfunction "VBAT_6") (pintype "passive"))
    )
    (net (code "96") (name "/VDDA") (class "Default")
      (node (ref "C11") (pin "2") (pinfunction "2_2") (pintype "passive"))
      (node (ref "C12") (pin "2") (pinfunction "2_2") (pintype "passive"))
      (node (ref "R3") (pin "1") (pinfunction "1_1") (pintype "passive"))
      (node (ref "U1") (pin "32") (pinfunction "Vref+_32") (pintype "passive"))
      (node (ref "U1") (pin "33") (pinfunction "VDDA_33") (pintype "passive"))
    )
    (net (code "97") (name "/WiFi_ANT") (class "Default")
      (node (ref "C13") (pin "2") (pinfunction "2_2") (pintype "passive"))
      (node (ref "C22") (pin "2") (pinfunction "2_2") (pintype "passive"))
      (node (ref "U7") (pin "17") (pinfunction "ANT_2.4G_17") (pintype "passive"))
    )
    (net (code "98") (name "/WiFi_Linked") (class "Default")
      (node (ref "LED2") (pin "2") (pinfunction "2_2") (pintype "passive"))
      (node (ref "R13") (pin "1") (pinfunction "1_1") (pintype "passive"))
      (node (ref "U7") (pin "13") (pinfunction "nLink_13") (pintype "passive"))
    )
    (net (code "99") (name "/WiFi_Reload") (class "Default")
      (node (ref "K1") (pin "2") (pinfunction "2_2") (pintype "passive"))
      (node (ref "R14") (pin "1") (pinfunction "1_1") (pintype "passive"))
      (node (ref "U7") (pin "12") (pinfunction "nReload_12") (pintype "passive"))
    )
    (net (code "100") (name "/WiFi_Reload(C10)") (class "Default")
      (node (ref "U1") (pin "111") (pinfunction "PC10/SPI3_SCK/U3_TX/U4_TX/SDIO_D2/DCMI_D8/I2S3_CK_111") (pintype "passive"))
    )
    (net (code "101") (name "/WiFi_Reload(E15)") (class "Default")
      (node (ref "R14") (pin "2") (pinfunction "2_2") (pintype "passive"))
      (node (ref "U1") (pin "68") (pinfunction "PE15/FSMC_D12/TIM1_BKIN_68") (pintype "passive"))
    )
    (net (code "102") (name "/Wifi_Connect(D11)") (class "Default")
      (node (ref "R13") (pin "2") (pinfunction "2_2") (pintype "passive"))
      (node (ref "U1") (pin "80") (pinfunction "PD11/FSMC_A16/FSMC_CLE/U3_CTS_80") (pintype "passive"))
    )
    (net (code "103") (name "3.3V") (class "Default")
      (node (ref "B1") (pin "1") (pinfunction "P_1") (pintype "passive"))
      (node (ref "C14") (pin "2") (pinfunction "2_2") (pintype "passive"))
      (node (ref "C15") (pin "2") (pinfunction "2_2") (pintype "passive"))
      (node (ref "C16") (pin "2") (pinfunction "2_2") (pintype "passive"))
      (node (ref "C17") (pin "2") (pinfunction "2_2") (pintype "passive"))
      (node (ref "C18") (pin "2") (pinfunction "2_2") (pintype "passive"))
      (node (ref "C19") (pin "2") (pinfunction "2_2") (pintype "passive"))
      (node (ref "C20") (pin "2") (pinfunction "2_2") (pintype "passive"))
      (node (ref "C21") (pin "2") (pinfunction "2_2") (pintype "passive"))
      (node (ref "C26") (pin "1") (pinfunction "1_1") (pintype "passive"))
      (node (ref "C3") (pin "1") (pinfunction "1_1") (pintype "passive"))
      (node (ref "C4") (pin "2") (pinfunction "2_2") (pintype "passive"))
      (node (ref "C8") (pin "1") (pinfunction "1_1") (pintype "passive"))
      (node (ref "D1") (pin "2") (pinfunction "2_2") (pintype "passive"))
      (node (ref "LED1") (pin "1") (pintype "passive"))
      (node (ref "P1") (pin "1") (pinfunction "1_1") (pintype "passive"))
      (node (ref "P3") (pin "2") (pinfunction "2_2") (pintype "passive"))
      (node (ref "P4") (pin "18") (pinfunction "18_18") (pintype "passive"))
      (node (ref "P6") (pin "11") (pinfunction "11_11") (pintype "passive"))
      (node (ref "P9") (pin "1") (pinfunction "1_1") (pintype "passive"))
      (node (ref "R11") (pin "2") (pinfunction "2_2") (pintype "passive"))
      (node (ref "R12") (pin "1") (pinfunction "1_1") (pintype "passive"))
      (node (ref "R15") (pin "1") (pinfunction "1_1") (pintype "passive"))
      (node (ref "R16") (pin "1") (pinfunction "1_1") (pintype "passive"))
      (node (ref "R2") (pin "2") (pinfunction "2_2") (pintype "passive"))
      (node (ref "R2") (pin "4") (pinfunction "4_4") (pintype "passive"))
      (node (ref "R3") (pin "2") (pinfunction "2_2") (pintype "passive"))
      (node (ref "R4") (pin "2") (pinfunction "2_2") (pintype "passive"))
      (node (ref "R5") (pin "1") (pinfunction "1_1") (pintype "passive"))
      (node (ref "R7") (pin "2") (pinfunction "2_2") (pintype "passive"))
      (node (ref "U1") (pin "108") (pinfunction "VDD_108") (pintype "passive"))
      (node (ref "U1") (pin "121") (pinfunction "VDD_121") (pintype "passive"))
      (node (ref "U1") (pin "131") (pinfunction "VDD_131") (pintype "passive"))
      (node (ref "U1") (pin "144") (pinfunction "VDD_144") (pintype "passive"))
      (node (ref "U1") (pin "17") (pinfunction "VDD_17") (pintype "passive"))
      (node (ref "U1") (pin "30") (pinfunction "VDD_30") (pintype "passive"))
      (node (ref "U1") (pin "39") (pinfunction "VDD_39") (pintype "passive"))
      (node (ref "U1") (pin "52") (pinfunction "VDD_52") (pintype "passive"))
      (node (ref "U1") (pin "62") (pinfunction "VDD_62") (pintype "passive"))
      (node (ref "U1") (pin "72") (pinfunction "VDD_72") (pintype "passive"))
      (node (ref "U1") (pin "84") (pinfunction "VDD_84") (pintype "passive"))
      (node (ref "U1") (pin "95") (pinfunction "VDD_95") (pintype "passive"))
      (node (ref "U2") (pin "2") (pinfunction "OUT_2") (pintype "passive"))
      (node (ref "U2") (pin "4") (pinfunction "OUT_4") (pintype "passive"))
      (node (ref "U5") (pin "11") (pinfunction "VCC_11") (pintype "passive"))
      (node (ref "U5") (pin "2") (pinfunction "VCC_2") (pintype "passive"))
      (node (ref "U6") (pin "3") (pinfunction "~{WP}_3") (pintype "passive"))
      (node (ref "U6") (pin "7") (pinfunction "~{RESET}_7") (pintype "passive"))
      (node (ref "U6") (pin "8") (pinfunction "VCC_8") (pintype "passive"))
      (node (ref "U7") (pin "15") (pinfunction "DVDD_15") (pintype "passive"))
      (node (ref "U8") (pin "2") (pinfunction "2_2") (pintype "passive"))
    )
    (net (code "104") (name "5.0V") (class "Default")
      (node (ref "C1") (pin "1") (pinfunction "1_1") (pintype "passive"))
      (node (ref "C2") (pin "2") (pinfunction "2_2") (pintype "passive"))
      (node (ref "C5") (pin "1") (pinfunction "1_1") (pintype "passive"))
      (node (ref "C6") (pin "1") (pinfunction "1_1") (pintype "passive"))
      (node (ref "F1") (pin "2") (pinfunction "2_2") (pintype "passive"))
      (node (ref "P7") (pin "1") (pinfunction "1_1") (pintype "passive"))
      (node (ref "R2") (pin "6") (pinfunction "6_6") (pintype "passive"))
      (node (ref "U2") (pin "3") (pinfunction "IN_3") (pintype "passive"))
      (node (ref "U3") (pin "7") (pinfunction "REG_7") (pintype "passive"))
      (node (ref "U3") (pin "8") (pinfunction "VBUS_8") (pintype "passive"))
    )
    (net (code "105") (name "GND") (class "Default")
      (node (ref "C1") (pin "2") (pinfunction "2_2") (pintype "passive"))
      (node (ref "C10") (pin "1") (pinfunction "1_1") (pintype "passive"))
      (node (ref "C11") (pin "1") (pinfunction "1_1") (pintype "passive"))
      (node (ref "C12") (pin "1") (pinfunction "1_1") (pintype "passive"))
      (node (ref "C14") (pin "1") (pinfunction "1_1") (pintype "passive"))
      (node (ref "C15") (pin "1") (pinfunction "1_1") (pintype "passive"))
      (node (ref "C16") (pin "1") (pinfunction "1_1") (pintype "passive"))
      (node (ref "C17") (pin "1") (pinfunction "1_1") (pintype "passive"))
      (node (ref "C18") (pin "1") (pinfunction "1_1") (pintype "passive"))
      (node (ref "C19") (pin "1") (pinfunction "1_1") (pintype "passive"))
      (node (ref "C2") (pin "1") (pinfunction "1_1") (pintype "passive"))
      (node (ref "C20") (pin "1") (pinfunction "1_1") (pintype "passive"))
      (node (ref "C21") (pin "1") (pinfunction "1_1") (pintype "passive"))
      (node (ref "C22") (pin "1") (pinfunction "1_1") (pintype "passive"))
      (node (ref "C23") (pin "1") (pinfunction "1_1") (pintype "passive"))
      (node (ref "C24") (pin "2") (pinfunction "2_2") (pintype "passive"))
      (node (ref "C25") (pin "2") (pinfunction "2_2") (pintype "passive"))
      (node (ref "C26") (pin "2") (pinfunction "2_2") (pintype "passive"))
      (node (ref "C3") (pin "2") (pinfunction "2_2") (pintype "passive"))
      (node (ref "C4") (pin "1") (pinfunction "1_1") (pintype "passive"))
      (node (ref "C5") (pin "2") (pinfunction "2_2") (pintype "passive"))
      (node (ref "C6") (pin "2") (pinfunction "2_2") (pintype "passive"))
      (node (ref "C7") (pin "2") (pinfunction "2_2") (pintype "passive"))
      (node (ref "C8") (pin "2") (pinfunction "2_2") (pintype "passive"))
      (node (ref "C9") (pin "1") (pinfunction "1_1") (pintype "passive"))
      (node (ref "D1") (pin "1") (pintype "passive"))
      (node (ref "J1") (pin "2") (pinfunction "GND_2") (pintype "passive"))
      (node (ref "J1") (pin "3") (pinfunction "GND_3") (pintype "passive"))
      (node (ref "K1") (pin "1") (pinfunction "1_1") (pintype "passive"))
      (node (ref "K2") (pin "2") (pinfunction "2_2") (pintype "passive"))
      (node (ref "K3") (pin "2") (pinfunction "2_2") (pintype "passive"))
      (node (ref "P1") (pin "4") (pinfunction "4_4") (pintype "passive"))
      (node (ref "P2") (pin "5") (pinfunction "B4_5") (pintype "passive"))
      (node (ref "P2") (pin "6") (pinfunction "B3_6") (pintype "passive"))
      (node (ref "P2") (pin "7") (pinfunction "B2_7") (pintype "passive"))
      (node (ref "P2") (pin "8") (pinfunction "B1_8") (pintype "passive"))
      (node (ref "P3") (pin "1") (pinfunction "1_1") (pintype "passive"))
      (node (ref "P4") (pin "2") (pinfunction "2_2") (pintype "passive"))
      (node (ref "P4") (pin "3") (pinfunction "3_3") (pintype "passive"))
      (node (ref "P6") (pin "10") (pinfunction "10_10") (pintype "passive"))
      (node (ref "P6") (pin "20") (pinfunction "20_20") (pintype "passive"))
      (node (ref "P7") (pin "2") (pinfunction "2_2") (pintype "passive"))
      (node (ref "P9") (pin "2") (pinfunction "2_2") (pintype "passive"))
      (node (ref "Q1") (pin "2") (pinfunction "E_2") (pintype "passive"))
      (node (ref "R1") (pin "1") (pinfunction "1_1") (pintype "passive"))
      (node (ref "R10") (pin "1") (pinfunction "TOP_1") (pintype "passive"))
      (node (ref "R2") (pin "8") (pinfunction "8_8") (pintype "passive"))
      (node (ref "R6") (pin "2") (pinfunction "2_2") (pintype "passive"))
      (node (ref "U1") (pin "107") (pinfunction "VSS_107") (pintype "passive"))
      (node (ref "U1") (pin "120") (pinfunction "VSS_120") (pintype "passive"))
      (node (ref "U1") (pin "130") (pinfunction "VSS_130") (pintype "passive"))
      (node (ref "U1") (pin "16") (pinfunction "VSS_16") (pintype "passive"))
      (node (ref "U1") (pin "31") (pinfunction "VSSA_31") (pintype "passive"))
      (node (ref "U1") (pin "38") (pinfunction "VSS_38") (pintype "passive"))
      (node (ref "U1") (pin "51") (pinfunction "VSS_51") (pintype "passive"))
      (node (ref "U1") (pin "61") (pinfunction "VSS_61") (pintype "passive"))
      (node (ref "U1") (pin "83") (pinfunction "VSS_83") (pintype "passive"))
      (node (ref "U1") (pin "94") (pinfunction "VSS_94") (pintype "passive"))
      (node (ref "U2") (pin "1") (pinfunction "GND_1") (pintype "passive"))
      (node (ref "U3") (pin "3") (pinfunction "GND_3") (pintype "passive"))
      (node (ref "U4") (pin "5") (pinfunction "GND_5") (pintype "power_in"))
      (node (ref "U5") (pin "5") (pinfunction "GND_5") (pintype "passive"))
      (node (ref "U5") (pin "8") (pinfunction "GND_8") (pintype "passive"))
      (node (ref "U6") (pin "4") (pinfunction "GND_4") (pintype "passive"))
      (node (ref "U7") (pin "16") (pinfunction "GND_16") (pintype "passive"))
      (node (ref "X1") (pin "3") (pinfunction "3_3") (pintype "passive"))
    )
    (net (code "106") (name "Net-(B1-G)") (class "Default")
      (node (ref "B1") (pin "2") (pinfunction "G_2") (pintype "passive"))
      (node (ref "Q1") (pin "3") (pinfunction "C_3") (pintype "passive"))
    )
    (net (code "107") (name "Net-(J1-ANT)") (class "Default")
      (node (ref "C13") (pin "1") (pinfunction "1_1") (pintype "passive"))
      (node (ref "C23") (pin "2") (pinfunction "2_2") (pintype "passive"))
      (node (ref "J1") (pin "1") (pinfunction "ANT_1") (pintype "passive"))
    )
    (net (code "108") (name "Net-(LED1-Pad2)") (class "Default")
      (node (ref "LED1") (pin "2") (pinfunction "2_2") (pintype "passive"))
      (node (ref "R1") (pin "2") (pinfunction "2_2") (pintype "passive"))
    )
    (net (code "109") (name "Net-(LED2-Pad1)") (class "Default")
      (node (ref "LED2") (pin "1") (pintype "passive"))
      (node (ref "R5") (pin "2") (pinfunction "2_2") (pintype "passive"))
    )
    (net (code "110") (name "Net-(Q1-B)") (class "Default")
      (node (ref "Q1") (pin "1") (pinfunction "B_1") (pintype "passive"))
      (node (ref "R8") (pin "7") (pinfunction "7_7") (pintype "passive"))
    )
    (net (code "111") (name "Net-(U1-PDR_ON)") (class "Default")
      (node (ref "R4") (pin "1") (pinfunction "1_1") (pintype "passive"))
      (node (ref "U1") (pin "143") (pinfunction "PDR_ON_143") (pintype "passive"))
    )
    (net (code "112") (name "Net-(U1-Vcap_1)") (class "Default")
      (node (ref "C9") (pin "2") (pinfunction "2_2") (pintype "passive"))
      (node (ref "U1") (pin "71") (pinfunction "Vcap_1_71") (pintype "passive"))
    )
    (net (code "113") (name "Net-(U1-Vcap_2)") (class "Default")
      (node (ref "C10") (pin "2") (pinfunction "2_2") (pintype "passive"))
      (node (ref "U1") (pin "106") (pinfunction "Vcap_2_106") (pintype "passive"))
    )
    (net (code "114") (name "Net-(U3-VDD)") (class "Default")
      (node (ref "C7") (pin "1") (pinfunction "1_1") (pintype "passive"))
      (node (ref "U3") (pin "6") (pinfunction "VDD_6") (pintype "passive"))
    )
    (net (code "115") (name "Net-(U8-B)") (class "Default")
      (node (ref "R8") (pin "1") (pinfunction "1_1") (pintype "passive"))
      (node (ref "U8") (pin "1") (pinfunction "B_1") (pintype "passive"))
    )
    (net (code "116") (name "Net-(U8-G)") (class "Default")
      (node (ref "R8") (pin "3") (pinfunction "3_3") (pintype "passive"))
      (node (ref "U8") (pin "3") (pinfunction "G_3") (pintype "passive"))
    )
    (net (code "117") (name "Net-(U8-R)") (class "Default")
      (node (ref "R8") (pin "5") (pinfunction "5_5") (pintype "passive"))
      (node (ref "U8") (pin "4") (pinfunction "R_4") (pintype "passive"))
    )
    (net (code "118") (name "POWER_5V_IN") (class "Default")
      (node (ref "F1") (pin "1") (pinfunction "1_1") (pintype "passive"))
      (node (ref "P4") (pin "19") (pinfunction "19_19") (pintype "passive"))
      (node (ref "U4") (pin "1") (pinfunction "VCC_1") (pintype "power_in"))
    )
    (net (code "119") (name "unconnected-(R10-BOT-Pad3)") (class "Default")
      (node (ref "R10") (pin "3") (pinfunction "BOT_3") (pintype "passive"))
    )
    (net (code "120") (name "unconnected-(U1-PA12{slash}TIM1_ETR{slash}U1_RTS{slash}CAN1_TX{slash}OTG_FS_DP-Pad104)") (class "Default")
      (node (ref "U1") (pin "104") (pinfunction "PA12/TIM1_ETR/U1_RTS/CAN1_TX/OTG_FS_DP_104") (pintype "passive"))
    )
    (net (code "121") (name "unconnected-(U1-PC13{slash}RTC_AF1-Pad7)") (class "Default")
      (node (ref "U1") (pin "7") (pinfunction "PC13/RTC_AF1_7") (pintype "passive+no_connect"))
    )
    (net (code "122") (name "unconnected-(U1-PC14-OSC32_IN-Pad8)") (class "Default")
      (node (ref "U1") (pin "8") (pinfunction "PC14-OSC32_IN_8") (pintype "passive+no_connect"))
    )
    (net (code "123") (name "unconnected-(U1-PC15-OSC32_OUT-Pad9)") (class "Default")
      (node (ref "U1") (pin "9") (pinfunction "PC15-OSC32_OUT_9") (pintype "passive+no_connect"))
    )
    (net (code "124") (name "unconnected-(U1-PD5{slash}FSMC_NWE{slash}U2_TX-Pad119)") (class "Default")
      (node (ref "U1") (pin "119") (pinfunction "PD5/FSMC_NWE/U2_TX_119") (pintype "passive+no_connect"))
    )
    (net (code "125") (name "unconnected-(U1-PE4{slash}TRACED1{slash}FSMC_A20{slash}DCMI_D4-Pad3)") (class "Default")
      (node (ref "U1") (pin "3") (pinfunction "PE4/TRACED1/FSMC_A20/DCMI_D4_3") (pintype "passive"))
    )
    (net (code "126") (name "unconnected-(U1-PE7{slash}FSMC_D4{slash}TIM1_ETR-Pad58)") (class "Default")
      (node (ref "U1") (pin "58") (pinfunction "PE7/FSMC_D4/TIM1_ETR_58") (pintype "passive"))
    )
    (net (code "127") (name "unconnected-(U1-PF2{slash}FSMC_A2{slash}I2C2_SMBA-Pad12)") (class "Default")
      (node (ref "U1") (pin "12") (pinfunction "PF2/FSMC_A2/I2C2_SMBA_12") (pintype "passive"))
    )
    (net (code "128") (name "unconnected-(U1-PF10{slash}FSMC_INTR{slash}ADC3_IN8-Pad22)") (class "Default")
      (node (ref "U1") (pin "22") (pinfunction "PF10/FSMC_INTR/ADC3_IN8_22") (pintype "passive"))
    )
    (net (code "129") (name "unconnected-(U1-PF11{slash}DCMI_D12-Pad49)") (class "Default")
      (node (ref "U1") (pin "49") (pinfunction "PF11/DCMI_D12_49") (pintype "passive"))
    )
    (net (code "130") (name "unconnected-(U1-PF12{slash}FSMC_A6-Pad50)") (class "Default")
      (node (ref "U1") (pin "50") (pinfunction "PF12/FSMC_A6_50") (pintype "passive"))
    )
    (net (code "131") (name "unconnected-(U1-PF13{slash}FSMC_A7-Pad53)") (class "Default")
      (node (ref "U1") (pin "53") (pinfunction "PF13/FSMC_A7_53") (pintype "passive"))
    )
    (net (code "132") (name "unconnected-(U1-PF14{slash}FSMC_A8-Pad54)") (class "Default")
      (node (ref "U1") (pin "54") (pinfunction "PF14/FSMC_A8_54") (pintype "passive"))
    )
    (net (code "133") (name "unconnected-(U1-PF15{slash}FSMC_A9-Pad55)") (class "Default")
      (node (ref "U1") (pin "55") (pinfunction "PF15/FSMC_A9_55") (pintype "passive"))
    )
    (net (code "134") (name "unconnected-(U1-PG0{slash}FSMC_A10-Pad56)") (class "Default")
      (node (ref "U1") (pin "56") (pinfunction "PG0/FSMC_A10_56") (pintype "passive"))
    )
    (net (code "135") (name "unconnected-(U1-PG1{slash}FSMC_A11-Pad57)") (class "Default")
      (node (ref "U1") (pin "57") (pinfunction "PG1/FSMC_A11_57") (pintype "passive"))
    )
    (net (code "136") (name "unconnected-(U1-PG2{slash}FSMC_A12-Pad87)") (class "Default")
      (node (ref "U1") (pin "87") (pinfunction "PG2/FSMC_A12_87") (pintype "passive"))
    )
    (net (code "137") (name "unconnected-(U1-PG4{slash}FSMC_A14-Pad89)") (class "Default")
      (node (ref "U1") (pin "89") (pinfunction "PG4/FSMC_A14_89") (pintype "passive"))
    )
    (net (code "138") (name "unconnected-(U1-PG5{slash}FSMC_A15-Pad90)") (class "Default")
      (node (ref "U1") (pin "90") (pinfunction "PG5/FSMC_A15_90") (pintype "passive"))
    )
    (net (code "139") (name "unconnected-(U1-PG6{slash}FSMC_INT2-Pad91)") (class "Default")
      (node (ref "U1") (pin "91") (pinfunction "PG6/FSMC_INT2_91") (pintype "passive"))
    )
    (net (code "140") (name "unconnected-(U1-PG7{slash}FSMC_INT3{slash}U6_CK-Pad92)") (class "Default")
      (node (ref "U1") (pin "92") (pinfunction "PG7/FSMC_INT3/U6_CK_92") (pintype "passive"))
    )
    (net (code "141") (name "unconnected-(U1-PG8{slash}U6_RTS{slash}ETH_PPS_OUT-Pad93)") (class "Default")
      (node (ref "U1") (pin "93") (pinfunction "PG8/U6_RTS/ETH_PPS_OUT_93") (pintype "passive"))
    )
    (net (code "142") (name "unconnected-(U1-PG14{slash}FSMC_A25{slash}U6_TX{slash}ETH_MII_TXD1{slash}ETH_RMII_TXD1-Pad129)") (class "Default")
      (node (ref "U1") (pin "129") (pinfunction "PG14/FSMC_A25/U6_TX/ETH_MII_TXD1/ETH_RMII_TXD1_129") (pintype "passive"))
    )
    (net (code "143") (name "unconnected-(U1-PG15{slash}U6_CTS{slash}DCMI_D13-Pad132)") (class "Default")
      (node (ref "U1") (pin "132") (pinfunction "PG15/U6_CTS/DCMI_D13_132") (pintype "passive"))
    )
    (net (code "144") (name "unconnected-(U3-CTS-Pad23)") (class "Default")
      (node (ref "U3") (pin "23") (pinfunction "CTS_23") (pintype "passive+no_connect"))
    )
    (net (code "145") (name "unconnected-(U3-DCO-Pad1)") (class "Default")
      (node (ref "U3") (pin "1") (pinfunction "DCO_1") (pintype "passive+no_connect"))
    )
    (net (code "146") (name "unconnected-(U3-DSR-Pad27)") (class "Default")
      (node (ref "U3") (pin "27") (pinfunction "DSR_27") (pintype "passive+no_connect"))
    )
    (net (code "147") (name "unconnected-(U3-DTR-Pad28)") (class "Default")
      (node (ref "U3") (pin "28") (pinfunction "DTR_28") (pintype "passive+no_connect"))
    )
    (net (code "148") (name "unconnected-(U3-NC-Pad10)") (class "Default")
      (node (ref "U3") (pin "10") (pinfunction "NC_10") (pintype "passive+no_connect"))
    )
    (net (code "149") (name "unconnected-(U3-NC-Pad13)") (class "Default")
      (node (ref "U3") (pin "13") (pinfunction "NC_13") (pintype "passive+no_connect"))
    )
    (net (code "150") (name "unconnected-(U3-NC-Pad14)") (class "Default")
      (node (ref "U3") (pin "14") (pinfunction "NC_14") (pintype "passive+no_connect"))
    )
    (net (code "151") (name "unconnected-(U3-NC-Pad15)") (class "Default")
      (node (ref "U3") (pin "15") (pinfunction "NC_15") (pintype "passive+no_connect"))
    )
    (net (code "152") (name "unconnected-(U3-NC-Pad16)") (class "Default")
      (node (ref "U3") (pin "16") (pinfunction "NC_16") (pintype "passive+no_connect"))
    )
    (net (code "153") (name "unconnected-(U3-NC-Pad17)") (class "Default")
      (node (ref "U3") (pin "17") (pinfunction "NC_17") (pintype "passive+no_connect"))
    )
    (net (code "154") (name "unconnected-(U3-NC-Pad19)") (class "Default")
      (node (ref "U3") (pin "19") (pinfunction "NC_19") (pintype "passive+no_connect"))
    )
    (net (code "155") (name "unconnected-(U3-NC-Pad20)") (class "Default")
      (node (ref "U3") (pin "20") (pinfunction "NC_20") (pintype "passive+no_connect"))
    )
    (net (code "156") (name "unconnected-(U3-NC-Pad21)") (class "Default")
      (node (ref "U3") (pin "21") (pinfunction "NC_21") (pintype "passive+no_connect"))
    )
    (net (code "157") (name "unconnected-(U3-NC-Pad22)") (class "Default")
      (node (ref "U3") (pin "22") (pinfunction "NC_22") (pintype "passive+no_connect"))
    )
    (net (code "158") (name "unconnected-(U3-RI-Pad2)") (class "Default")
      (node (ref "U3") (pin "2") (pinfunction "RI_2") (pintype "passive+no_connect"))
    )
    (net (code "159") (name "unconnected-(U3-RTS-Pad24)") (class "Default")
      (node (ref "U3") (pin "24") (pinfunction "RTS_24") (pintype "passive+no_connect"))
    )
    (net (code "160") (name "unconnected-(U3-SUS-Pad12)") (class "Default")
      (node (ref "U3") (pin "12") (pinfunction "SUS_12") (pintype "passive+no_connect"))
    )
    (net (code "161") (name "unconnected-(U3-VPP-Pad18)") (class "Default")
      (node (ref "U3") (pin "18") (pinfunction "VPP_18") (pintype "passive+no_connect"))
    )
    (net (code "162") (name "unconnected-(U4-ID-Pad4)") (class "Default")
      (node (ref "U4") (pin "4") (pinfunction "ID_4") (pintype "power_in"))
    )
    (net (code "163") (name "unconnected-(U5-D0-Pad1)") (class "Default")
      (node (ref "U5") (pin "1") (pinfunction "D0_1") (pintype "passive"))
    )
    (net (code "164") (name "unconnected-(U5-D1-Pad6)") (class "Default")
      (node (ref "U5") (pin "6") (pinfunction "D1_6") (pintype "passive"))
    )
    (net (code "165") (name "unconnected-(U5-D2-Pad12)") (class "Default")
      (node (ref "U5") (pin "12") (pinfunction "D2_12") (pintype "passive"))
    )
    (net (code "166") (name "unconnected-(U5-D3-Pad7)") (class "Default")
      (node (ref "U5") (pin "7") (pinfunction "D3_7") (pintype "passive"))
    )
    (net (code "167") (name "unconnected-(U7-GPIO1-Pad1)") (class "Default")
      (node (ref "U7") (pin "1") (pinfunction "GPIO1_1") (pintype "passive"))
    )
    (net (code "168") (name "unconnected-(U7-GPIO2-Pad2)") (class "Default")
      (node (ref "U7") (pin "2") (pinfunction "GPIO2_2") (pintype "passive"))
    )
    (net (code "169") (name "unconnected-(U7-GPIO3-Pad3)") (class "Default")
      (node (ref "U7") (pin "3") (pinfunction "GPIO3_3") (pintype "passive"))
    )
    (net (code "170") (name "unconnected-(U7-GPIO4-Pad4)") (class "Default")
      (node (ref "U7") (pin "4") (pinfunction "GPIO4_4") (pintype "passive"))
    )
    (net (code "171") (name "unconnected-(U7-UART0_CTS-Pad7)") (class "Default")
      (node (ref "U7") (pin "7") (pinfunction "UART0_CTS_7") (pintype "passive"))
    )
    (net (code "172") (name "unconnected-(U7-UART0_RTS-Pad8)") (class "Default")
      (node (ref "U7") (pin "8") (pinfunction "UART0_RTS_8") (pintype "passive"))
    )
    (net (code "173") (name "unconnected-(U7-WPS-Pad9)") (class "Default")
      (node (ref "U7") (pin "9") (pinfunction "WPS_9") (pintype "passive"))
    )
    (net (code "174") (name "unconnected-(U7-WPS-Pad14)") (class "Default")
      (node (ref "U7") (pin "14") (pinfunction "WPS_14") (pintype "passive"))
    )
    (net (code "175") (name "unconnected-(U7-nReady-Pad11)") (class "Default")
      (node (ref "U7") (pin "11") (pinfunction "nReady_11") (pintype "passive"))
    )
    (net (code "176") (name "unconnected-(U7-nReset-Pad10)") (class "Default")
      (node (ref "U7") (pin "10") (pinfunction "nReset_10") (pintype "passive"))
    )
  )
)
